# eagle_sketch.net
KiCad netlist of a schematic drawn in EAGLE
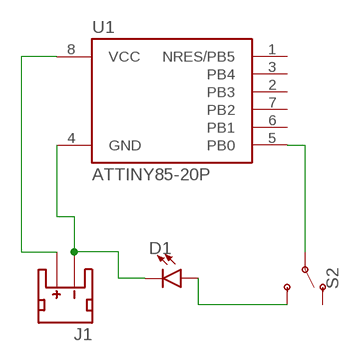
[diagram p0: schematic, sheet 1]

(export (version "E")
  (design (tool "Eeschema 10.0.6"))
  (components
    (comp (ref "D1")
      (value "LED3MM")
      (footprint "eagle-import:LED_3MM")
      (libsource (lib "eagle-import") (part "LED3MM"))
    )
    (comp (ref "J1")
      (value "JST_2MM_MALE")
      (footprint "eagle-import:JST-2-SMD")
      (libsource (lib "eagle-import") (part "JST_2MM_MALE"))
    )
    (comp (ref "S2")
      (value "SWITCH-SPDT-PTH-11.6X4.0MM")
      (footprint "eagle-import:SWITCH_SPDT_PTH_11.6X4.0MM")
      (libsource (lib "eagle-import") (part "SWITCH-SPDT-PTH-11.6X4.0MM"))
    )
    (comp (ref "U1")
      (value "ATTINY85-20P")
      (footprint "eagle-import:PDIP08_300MIL")
      (libsource (lib "eagle-import") (part "ATTINY85P-20"))
    )
  )
  (nets
    (net (code "1") (name "Net-(D1-C)") (class "Default")
      (node (ref "D1") (pin "K") (pinfunction "C_K") (pintype "passive"))
      (node (ref "J1") (pin "1") (pinfunction "-_1") (pintype "bidirectional"))
      (node (ref "U1") (pin "4") (pinfunction "GND_4") (pintype "power_in"))
    )
    (net (code "2") (name "Net-(J1-+)") (class "Default")
      (node (ref "J1") (pin "2") (pinfunction "+_2") (pintype "bidirectional"))
      (node (ref "U1") (pin "8") (pinfunction "VCC_8") (pintype "power_in"))
    )
    (net (code "3") (name "Net-(S2-P)") (class "Default")
      (node (ref "S2") (pin "2") (pinfunction "P_2") (pintype "passive"))
      (node (ref "U1") (pin "5") (pinfunction "PB0_5") (pintype "bidirectional"))
    )
    (net (code "4") (name "Net-(S2-S)") (class "Default")
      (node (ref "D1") (pin "A") (pinfunction "A_A") (pintype "passive"))
      (node (ref "S2") (pin "3") (pinfunction "S_3") (pintype "passive"))
    )
    (net (code "5") (name "unconnected-(J1-PAD1-PadNC1)") (class "Default")
      (node (ref "J1") (pin "NC1") (pinfunction "PAD1_NC1") (pintype "bidirectional"))
    )
    (net (code "6") (name "unconnected-(J1-PAD2-PadNC2)") (class "Default")
      (node (ref "J1") (pin "NC2") (pinfunction "PAD2_NC2") (pintype "bidirectional"))
    )
    (net (code "7") (name "unconnected-(S2-O-Pad1)") (class "Default")
      (node (ref "S2") (pin "1") (pinfunction "O_1") (pintype "passive"))
    )
    (net (code "8") (name "unconnected-(U1-NRES{slash}PB5-Pad1)") (class "Default")
      (node (ref "U1") (pin "1") (pinfunction "NRES/PB5_1") (pintype "bidirectional"))
    )
    (net (code "9") (name "unconnected-(U1-PB1-Pad6)") (class "Default")
      (node (ref "U1") (pin "6") (pinfunction "PB1_6") (pintype "bidirectional"))
    )
    (net (code "10") (name "unconnected-(U1-PB2-Pad7)") (class "Default")
      (node (ref "U1") (pin "7") (pinfunction "PB2_7") (pintype "bidirectional"))
    )
    (net (code "11") (name "unconnected-(U1-PB3-Pad2)") (class "Default")
      (node (ref "U1") (pin "2") (pinfunction "PB3_2") (pintype "bidirectional"))
    )
    (net (code "12") (name "unconnected-(U1-PB4-Pad3)") (class "Default")
      (node (ref "U1") (pin "3") (pinfunction "PB4_3") (pintype "bidirectional"))
    )
  )
)
